# PowerStage.net
KiCad netlist of a schematic drawn in Altium Designer
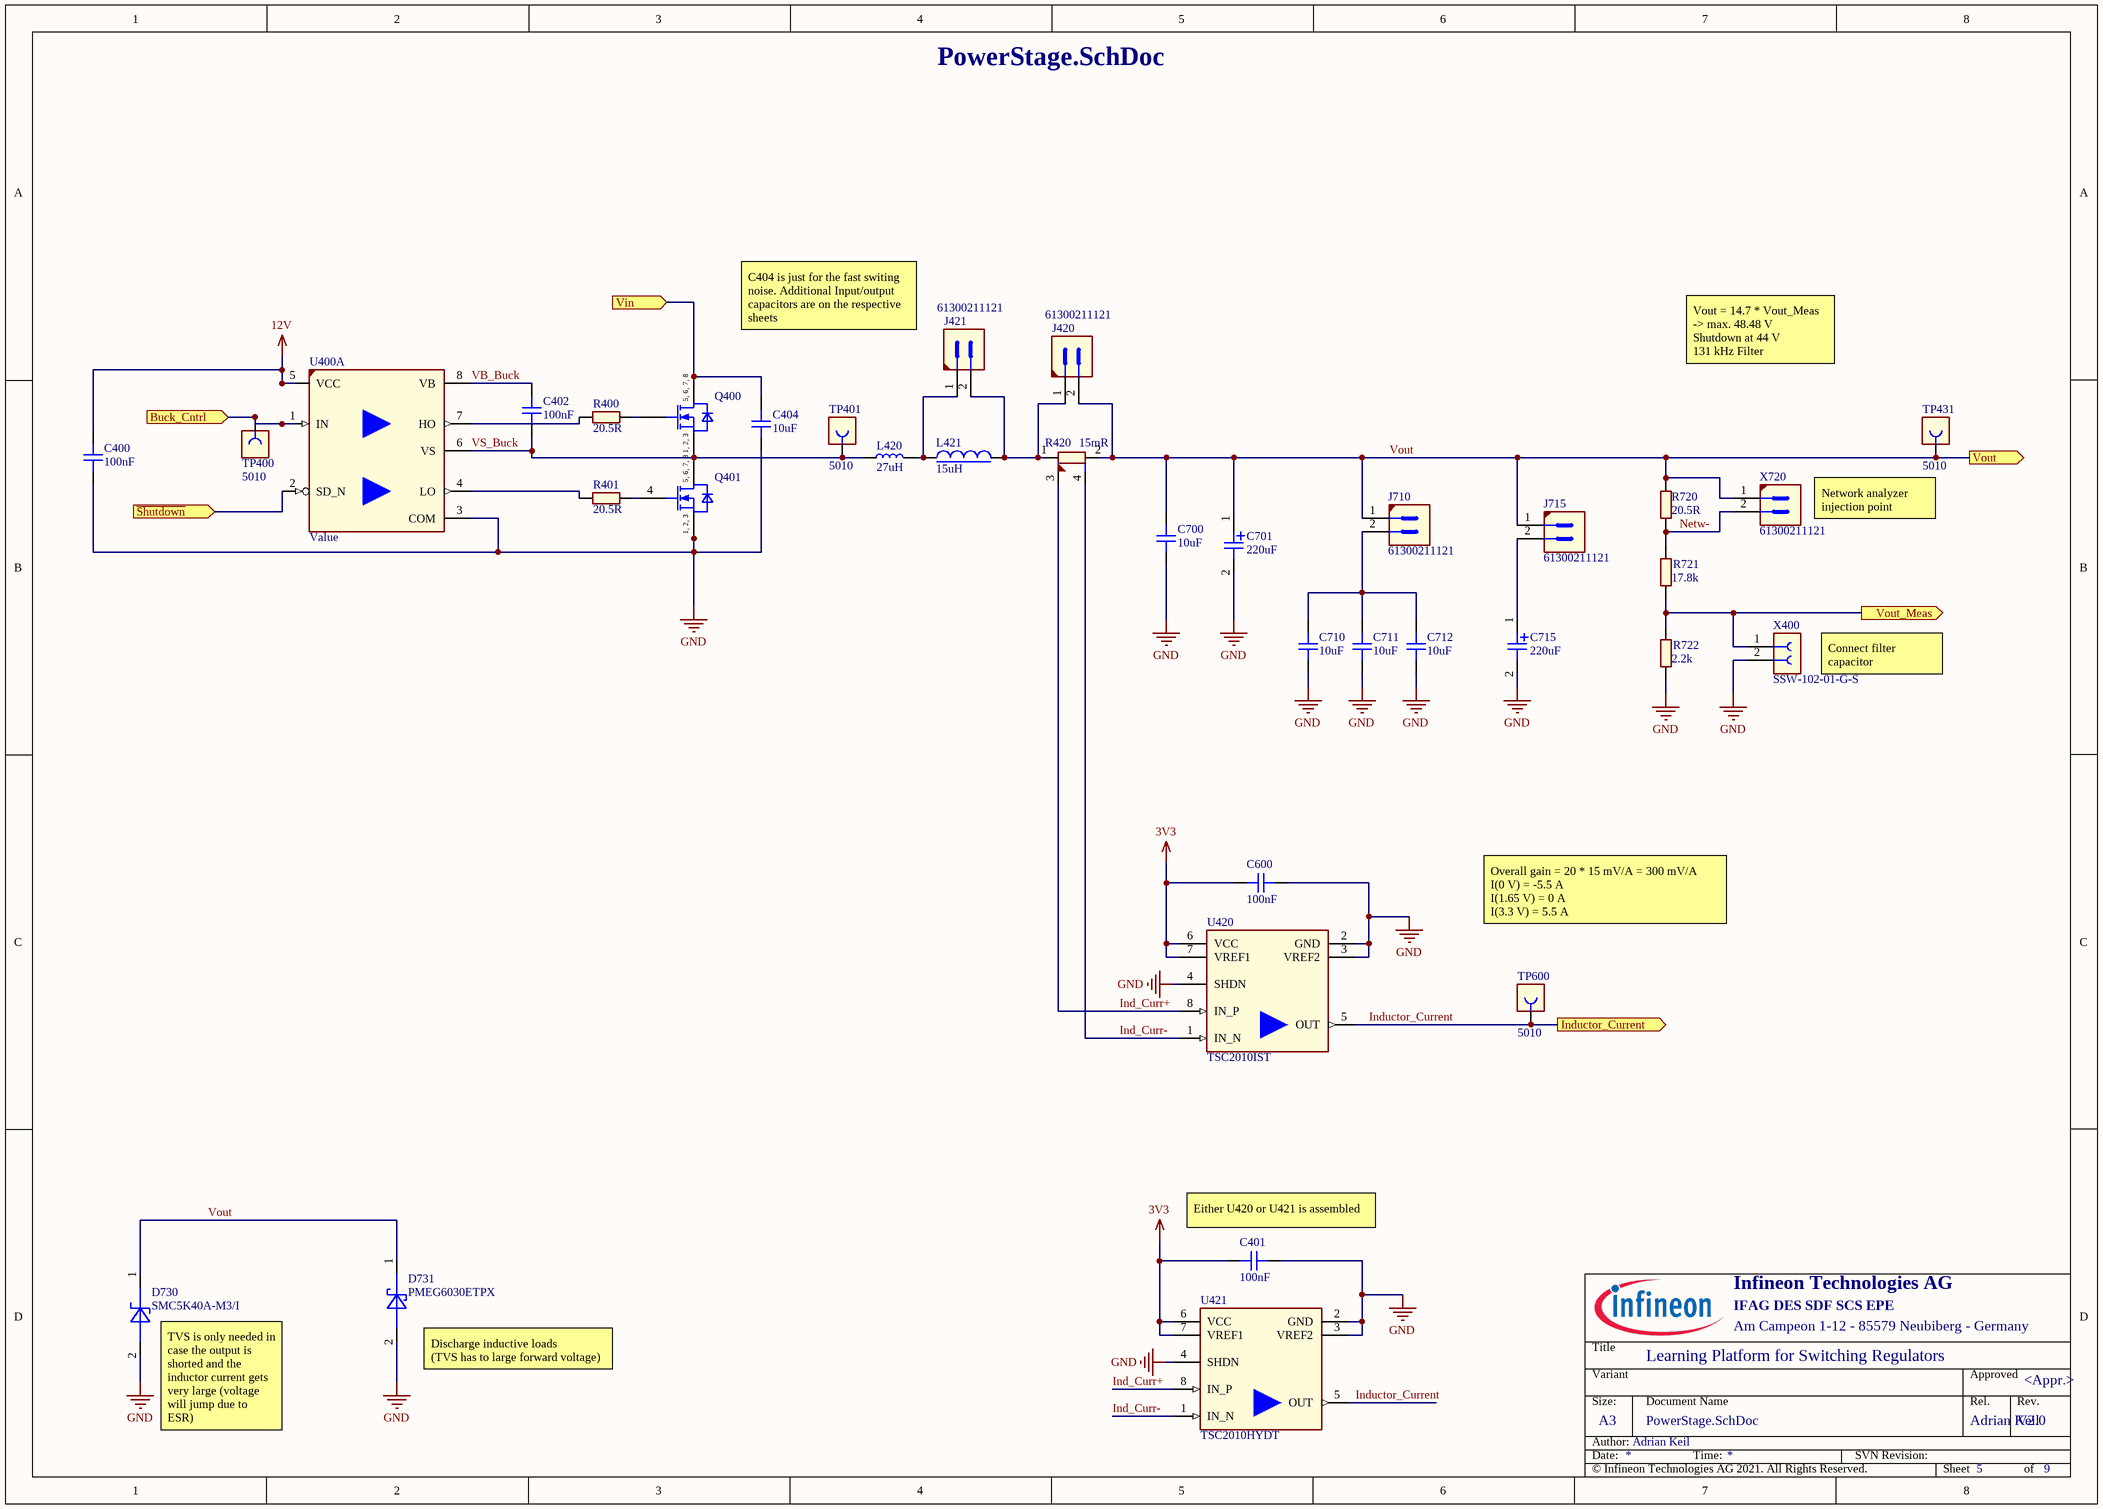
[diagram p0: PowerStage.SchDoc]

(export (version "E")
  (design (tool "Eeschema 10.0.6"))
  (components
    (comp (ref "C400")
      (value "100nF")
      (footprint "CAPC3216X125N-0")
      (description "CAP / CERA / 100nF / 50V / 10% / X7R (EIA) / -55°C to 125°C / 1206(3216) / SMD / -")
      (fields (field (name "LEGACY PARTNUMBER") "CAP01005660") (field (name "MANUFACTURER") "MuRata"))
      (libsource (lib "PCBLibraryData") (part "CAP-SGL-STD-02P_00000001"))
    )
    (comp (ref "C401")
      (value "100nF")
      (footprint "CAPC3216X125N-0")
      (description "CAP / CERA / 100nF / 50V / 10% / X7R (EIA) / -55°C to 125°C / 1206(3216) / SMD / -")
      (fields (field (name "LEGACY PARTNUMBER") "CAP01005660") (field (name "MANUFACTURER") "MuRata"))
      (libsource (lib "PCBLibraryData") (part "CAP-SGL-STD-02P_00000001"))
    )
    (comp (ref "C402")
      (value "100nF")
      (footprint "CAPC3216X125N-0")
      (description "CAP / CERA / 100nF / 50V / 10% / X7R (EIA) / -55°C to 125°C / 1206(3216) / SMD / -")
      (fields (field (name "LEGACY PARTNUMBER") "CAP01005660") (field (name "MANUFACTURER") "MuRata"))
      (libsource (lib "PCBLibraryData") (part "CAP-SGL-STD-02P_00000001"))
    )
    (comp (ref "C404")
      (value "10uF")
      (footprint "CAPC3216X190N-1")
      (description "CAP / CERA / 10uF / 50V / 20% / X5R (EIA) / -55°C to 85°C / 1206 (3216) / SMD / -")
      (fields (field (name "MANUFACTURER") "Taiyo Yuden"))
      (libsource (lib "PCBLibraryData") (part "CAP-SGL-STD-02P_00000001"))
    )
    (comp (ref "C600")
      (value "100nF")
      (footprint "CAPC3216X125N-0")
      (description "CAP / CERA / 100nF / 50V / 10% / X7R (EIA) / -55°C to 125°C / 1206(3216) / SMD / -")
      (fields (field (name "LEGACY PARTNUMBER") "CAP01005660") (field (name "MANUFACTURER") "MuRata"))
      (libsource (lib "PCBLibraryData") (part "CAP-SGL-STD-02P_00000001"))
    )
    (comp (ref "C700")
      (value "10uF")
      (footprint "CAPC3216X190N-1")
      (description "CAP / CERA / 10uF / 50V / 20% / X5R (EIA) / -55°C to 85°C / 1206 (3216) / SMD / -")
      (fields (field (name "MANUFACTURER") "Taiyo Yuden"))
      (libsource (lib "PCBLibraryData") (part "CAP-SGL-STD-02P_00000001"))
    )
    (comp (ref "C701")
      (value "220uF")
      (footprint "CAPAE1030X1050N-3")
      (fields (field (name "MANUFACTURER") "Nippon Chemi-Con"))
      (libsource (lib "PCBLibraryData") (part "CAP-SGL-POL-02P_00000002"))
    )
    (comp (ref "C710")
      (value "10uF")
      (footprint "CAPC3216X190N-1")
      (description "CAP / CERA / 10uF / 50V / 20% / X5R (EIA) / -55°C to 85°C / 1206 (3216) / SMD / -")
      (fields (field (name "MANUFACTURER") "Taiyo Yuden"))
      (libsource (lib "PCBLibraryData") (part "CAP-SGL-STD-02P_00000001"))
    )
    (comp (ref "C711")
      (value "10uF")
      (footprint "CAPC3216X190N-1")
      (description "CAP / CERA / 10uF / 50V / 20% / X5R (EIA) / -55°C to 85°C / 1206 (3216) / SMD / -")
      (fields (field (name "MANUFACTURER") "Taiyo Yuden"))
      (libsource (lib "PCBLibraryData") (part "CAP-SGL-STD-02P_00000001"))
    )
    (comp (ref "C712")
      (value "10uF")
      (footprint "CAPC3216X190N-1")
      (description "CAP / CERA / 10uF / 50V / 20% / X5R (EIA) / -55°C to 85°C / 1206 (3216) / SMD / -")
      (fields (field (name "MANUFACTURER") "Taiyo Yuden"))
      (libsource (lib "PCBLibraryData") (part "CAP-SGL-STD-02P_00000001"))
    )
    (comp (ref "C715")
      (value "220uF")
      (footprint "CAPAE1030X1050N-3")
      (fields (field (name "MANUFACTURER") "Nippon Chemi-Con"))
      (libsource (lib "PCBLibraryData") (part "CAP-SGL-POL-02P_00000002"))
    )
    (comp (ref "D730")
      (value "SMC5K40A-M3/I")
      (footprint "DIOM7959X262N")
      (description "Surface Mount Transient Voltage Suppressors, Unidirectional, Very Fast Response Time")
      (fields (field (name "MANUFACTURER") "Vishay"))
      (libsource (lib "PCBLibraryData") (part "d_tvs_a"))
    )
    (comp (ref "D731")
      (value "PMEG6030ETPX")
      (footprint "SODFL4725X110N")
      (description "DIODE SCHOTTKY 60V 3A SOD128")
      (fields (field (name "MANUFACTURER") "Nexperia"))
      (libsource (lib "PCBLibraryData") (part "d_schottky_a"))
    )
    (comp (ref "J420")
      (value "61300211121")
      (footprint "CON-M-THT-61300211121")
      (description "Header, 2.54mm Pitch, 2 pin, Vertical, Single Row")
      (fields
        (field (name "LEGACY PARTNUMBER") "CON01500943")
        (field (name "MANUFACTURER") "Wurth Elektronik")
      )
      (libsource (lib "") (part "Header 2_1"))
    )
    (comp (ref "J421")
      (value "61300211121")
      (footprint "CON-M-THT-61300211121")
      (description "Header, 2.54mm Pitch, 2 pin, Vertical, Single Row")
      (fields
        (field (name "LEGACY PARTNUMBER") "CON01500943")
        (field (name "MANUFACTURER") "Wurth Elektronik")
      )
      (libsource (lib "") (part "Header 2_1"))
    )
    (comp (ref "J710")
      (value "61300211121")
      (footprint "CON-M-THT-61300211121")
      (description "Header, 2.54mm Pitch, 2 pin, Vertical, Single Row")
      (fields
        (field (name "LEGACY PARTNUMBER") "CON01500943")
        (field (name "MANUFACTURER") "Wurth Elektronik")
      )
      (libsource (lib "PCBLibraryData") (part "Header 2"))
    )
    (comp (ref "J715")
      (value "61300211121")
      (footprint "CON-M-THT-61300211121")
      (description "Header, 2.54mm Pitch, 2 pin, Vertical, Single Row")
      (fields
        (field (name "LEGACY PARTNUMBER") "CON01500943")
        (field (name "MANUFACTURER") "Wurth Elektronik")
      )
      (libsource (lib "PCBLibraryData") (part "Header 2"))
    )
    (comp (ref "L420")
      (value "27uH")
      (footprint "INDM120120X1000N")
      (fields (field (name "MANUFACTURER") "Wurth Elektronik"))
      (libsource (lib "PCBLibraryData") (part "IND-SGL-STD-02P_00000015"))
    )
    (comp (ref "L421")
      (value "15uH")
      (footprint "IND-SMD-SRP6060FA")
      (fields (field (name "MANUFACTURER") "Bourns"))
      (libsource (lib "PCBLibraryData") (part "IND-SGL-STD-COR-02P_00000016"))
    )
    (comp (ref "Q400")
      (value "igfet_n_ch_enh_dio_1s2s3s4g5d6d7d8d_8p")
      (footprint "INF-PG-PQFN-5X6BEG")
      (description "HEXFET Power MOSFET, VDS 60V, RDS(on) max 14.4 mO")
      (fields (field (name "MANUFACTURER") "Infineon Technologies"))
      (libsource (lib "") (part "igfet_n_ch_enh_dio_1s2s3s4g5d6d7d8d_8p_1"))
    )
    (comp (ref "Q401")
      (value "igfet_n_ch_enh_dio_1s2s3s4g5d6d7d8d_8p")
      (footprint "INF-PG-PQFN-5X6BEG")
      (description "HEXFET Power MOSFET, VDS 60V, RDS(on) max 14.4 mO")
      (fields (field (name "MANUFACTURER") "Infineon Technologies"))
      (libsource (lib "PCBLibraryData") (part "igfet_n_ch_enh_dio_1s2s3s4g5d6d7d8d_8p"))
    )
    (comp (ref "R400")
      (value "20.5R")
      (footprint "RESC3216X60N")
      (description "RES / STD / 20.5R / 250mW / 1% / 100ppm/K / -55°C to 155°C / 1206(3216) / SMD / -")
      (fields (field (name "LEGACY PARTNUMBER") "RES01802548") (field (name "MANUFACTURER") "Vishay"))
      (libsource (lib "") (part "RES-SGL-STD-02P_00000006_1"))
    )
    (comp (ref "R401")
      (value "20.5R")
      (footprint "RESC3216X60N")
      (description "RES / STD / 20.5R / 250mW / 1% / 100ppm/K / -55°C to 155°C / 1206(3216) / SMD / -")
      (fields (field (name "LEGACY PARTNUMBER") "RES01802548") (field (name "MANUFACTURER") "Vishay"))
      (libsource (lib "") (part "RES-SGL-STD-02P_00000006_1"))
    )
    (comp (ref "R420")
      (value "15mR")
      (footprint "RES-SMD-L4T12")
      (description "RES / STD / 15mR / 500mW / 1% / 75ppm/K / -55°C to 155°C / 1206 (3216) / SMD / -")
      (fields (field (name "MANUFACTURER") "Ohmite"))
      (libsource (lib "PCBLibraryData") (part "RES-SHT-STD-04P_00097BE5"))
    )
    (comp (ref "R720")
      (value "20.5R")
      (footprint "RESC3216X60N")
      (description "RES / STD / 20.5R / 250mW / 1% / 100ppm/K / -55°C to 155°C / 1206(3216) / SMD / -")
      (fields (field (name "LEGACY PARTNUMBER") "RES01802548") (field (name "MANUFACTURER") "Vishay"))
      (libsource (lib "PCBLibraryData") (part "RES-SGL-STD-02P_00000006"))
    )
    (comp (ref "R721")
      (value "17.8k")
      (footprint "RESC3216X60N")
      (description "RES / STD / 17.8k / 250mW / 1% / 100ppm/K / -55°C to 155°C / 1206(3216) / SMD / -")
      (fields (field (name "LEGACY PARTNUMBER") "RES01802883") (field (name "MANUFACTURER") "Vishay"))
      (libsource (lib "PCBLibraryData") (part "RES-SGL-STD-02P_00000006"))
    )
    (comp (ref "R722")
      (value "2.2k")
      (footprint "RESC3216X60N")
      (description "RES / STD / 2.2k / 250mW / 1% / 100ppm/K / -55°C to 155°C / 1206(3216) / SMD / -")
      (fields (field (name "LEGACY PARTNUMBER") "RES01802779") (field (name "MANUFACTURER") "Vishay"))
      (libsource (lib "") (part "RES-SGL-STD-02P_00000006_2"))
    )
    (comp (ref "TP400")
      (value "5010")
      (footprint "CON-THT-TP-5010")
      (description "PC Test Point-Multipurpose THT, Red")
      (fields
        (field (name "LEGACY PARTNUMBER") "CON01500529")
        (field (name "MANUFACTURER") "Keystone Electronics Corp.")
      )
      (libsource (lib "") (part "connector_1_f_1"))
    )
    (comp (ref "TP401")
      (value "5010")
      (footprint "CON-THT-TP-5010")
      (description "PC Test Point-Multipurpose THT, Red")
      (fields
        (field (name "LEGACY PARTNUMBER") "CON01500529")
        (field (name "MANUFACTURER") "Keystone Electronics Corp.")
      )
      (libsource (lib "PCBLibraryData") (part "connector_1_f"))
    )
    (comp (ref "TP431")
      (value "5010")
      (footprint "CON-THT-TP-5010")
      (description "PC Test Point-Multipurpose THT, Red")
      (fields
        (field (name "LEGACY PARTNUMBER") "CON01500529")
        (field (name "MANUFACTURER") "Keystone Electronics Corp.")
      )
      (libsource (lib "PCBLibraryData") (part "connector_1_f"))
    )
    (comp (ref "TP600")
      (value "5010")
      (footprint "CON-THT-TP-5010")
      (description "PC Test Point-Multipurpose THT, Red")
      (fields
        (field (name "LEGACY PARTNUMBER") "CON01500529")
        (field (name "MANUFACTURER") "Keystone Electronics Corp.")
      )
      (libsource (lib "PCBLibraryData") (part "connector_1_f"))
    )
    (comp (ref "U400")
      (value "Value")
      (footprint "SOIC127P600X172-8N-1-V")
      (description "Driving IGBTs, enhancement mode N-Channel MOSFETs in various power electronic applications")
      (fields (field (name "MANUFACTURER") "Infineon Technologies"))
      (libsource (lib "PCBLibraryData") (part "2ED2184S06F"))
    )
    (comp (ref "U420")
      (value "TSC2010IST")
      (footprint "SOIC127P600X175-8N-16")
      (description "Precision bidirectional current sense amplifier")
      (fields (field (name "MANUFACTURER") "STMicroelectronics"))
      (libsource (lib "PCBLibraryData") (part "TSC201XHYDT"))
    )
    (comp (ref "U421")
      (value "TSC2010HYDT")
      (footprint "SOIC127P600X175-8N-16")
      (description "Precision bidirectional current sense amplifier")
      (fields (field (name "MANUFACTURER") "STMicroelectronics"))
      (libsource (lib "PCBLibraryData") (part "TSC201XHYDT"))
    )
    (comp (ref "X400")
      (value "SSW-102-01-G-S")
      (footprint "CON-F-THT-SSW-102-01-G-S")
      (description "Through Hole .025'' SQ Post Socket, 2.54mm pitch, 2 Pins")
      (fields (field (name "MANUFACTURER") "Samtec"))
      (libsource (lib "PCBLibraryData") (part "Socket 2"))
    )
    (comp (ref "X720")
      (value "61300211121")
      (footprint "CON-M-THT-61300211121")
      (description "Header, 2.54mm Pitch, 2 pin, Vertical, Single Row")
      (fields
        (field (name "LEGACY PARTNUMBER") "CON01500943")
        (field (name "MANUFACTURER") "Wurth Elektronik")
      )
      (libsource (lib "PCBLibraryData") (part "Header 2"))
    )
  )
  (nets
    (net (code "1") (name "/Buck_Cntrl") (class "Default")
      (node (ref "TP400") (pin "1") (pinfunction "1_1") (pintype "passive"))
      (node (ref "U400") (pin "1") (pinfunction "IN_1") (pintype "input"))
    )
    (net (code "2") (name "/Ind_Curr+") (class "Default")
      (node (ref "R420") (pin "3") (pinfunction "I1_3") (pintype "passive"))
      (node (ref "U420") (pin "8") (pinfunction "IN_P_8") (pintype "input"))
      (node (ref "U421") (pin "8") (pinfunction "IN_P_8") (pintype "input"))
    )
    (net (code "3") (name "/Ind_Curr-") (class "Default")
      (node (ref "R420") (pin "4") (pinfunction "I2_4") (pintype "passive"))
      (node (ref "U420") (pin "1") (pinfunction "IN_N_1") (pintype "input"))
      (node (ref "U421") (pin "1") (pinfunction "IN_N_1") (pintype "input"))
    )
    (net (code "4") (name "/Inductor_Current") (class "Default")
      (node (ref "TP600") (pin "1") (pinfunction "1_1") (pintype "passive"))
      (node (ref "U420") (pin "5") (pinfunction "OUT_5") (pintype "output"))
      (node (ref "U421") (pin "5") (pinfunction "OUT_5") (pintype "output"))
    )
    (net (code "5") (name "/Netw-") (class "Default")
      (node (ref "R720") (pin "1") (pinfunction "1_1") (pintype "passive"))
      (node (ref "R721") (pin "2") (pinfunction "2_2") (pintype "passive"))
      (node (ref "X720") (pin "2") (pinfunction "2_2") (pintype "passive"))
    )
    (net (code "6") (name "/Shutdown") (class "Default")
      (node (ref "U400") (pin "2") (pinfunction "SD_N_2") (pintype "input"))
    )
    (net (code "7") (name "/VB_Buck") (class "Default")
      (node (ref "C402") (pin "2") (pinfunction "2_2") (pintype "passive"))
      (node (ref "U400") (pin "8") (pinfunction "VB_8") (pintype "power_in"))
    )
    (net (code "8") (name "/VS_Buck") (class "Default")
      (node (ref "C402") (pin "1") (pinfunction "1_1") (pintype "passive"))
      (node (ref "L420") (pin "1") (pinfunction "1_1") (pintype "passive"))
      (node (ref "Q400") (pin "1") (pinfunction "SOURCE_1") (pintype "passive"))
      (node (ref "Q400") (pin "2") (pinfunction "SOURCE_2") (pintype "passive"))
      (node (ref "Q400") (pin "3") (pinfunction "SOURCE_3") (pintype "passive"))
      (node (ref "Q401") (pin "5") (pinfunction "DRAIN_5") (pintype "passive"))
      (node (ref "Q401") (pin "6") (pinfunction "DRAIN_6") (pintype "passive"))
      (node (ref "Q401") (pin "7") (pinfunction "DRAIN_7") (pintype "passive"))
      (node (ref "Q401") (pin "8") (pinfunction "DRAIN_8") (pintype "passive"))
      (node (ref "TP401") (pin "1") (pinfunction "1_1") (pintype "passive"))
      (node (ref "U400") (pin "6") (pinfunction "VS_6") (pintype "power_in"))
    )
    (net (code "9") (name "/Vin") (class "Default")
      (node (ref "C404") (pin "2") (pinfunction "2_2") (pintype "passive"))
      (node (ref "Q400") (pin "5") (pinfunction "DRAIN_5") (pintype "passive"))
      (node (ref "Q400") (pin "6") (pinfunction "DRAIN_6") (pintype "passive"))
      (node (ref "Q400") (pin "7") (pinfunction "DRAIN_7") (pintype "passive"))
      (node (ref "Q400") (pin "8") (pinfunction "DRAIN_8") (pintype "passive"))
    )
    (net (code "10") (name "/Vout") (class "Default")
      (node (ref "C700") (pin "2") (pinfunction "2_2") (pintype "passive"))
      (node (ref "C701") (pin "1") (pinfunction "1_1") (pintype "passive"))
      (node (ref "D730") (pin "1") (pinfunction "CATHODE_1") (pintype "passive"))
      (node (ref "D731") (pin "1") (pinfunction "Cathode_1") (pintype "passive"))
      (node (ref "J420") (pin "2") (pinfunction "2_2") (pintype "passive"))
      (node (ref "J710") (pin "1") (pinfunction "1_1") (pintype "passive"))
      (node (ref "J715") (pin "1") (pinfunction "1_1") (pintype "passive"))
      (node (ref "R420") (pin "2") (pinfunction "V2_2") (pintype "passive"))
      (node (ref "R720") (pin "2") (pinfunction "2_2") (pintype "passive"))
      (node (ref "TP431") (pin "1") (pinfunction "1_1") (pintype "passive"))
      (node (ref "X720") (pin "1") (pinfunction "1_1") (pintype "passive"))
    )
    (net (code "11") (name "/Vout_Meas") (class "Default")
      (node (ref "R721") (pin "1") (pinfunction "1_1") (pintype "passive"))
      (node (ref "R722") (pin "1") (pinfunction "1_1") (pintype "passive"))
      (node (ref "X400") (pin "1") (pinfunction "1_1") (pintype "passive"))
    )
    (net (code "12") (name "3V3") (class "Default")
      (node (ref "C401") (pin "2") (pinfunction "2_2") (pintype "passive"))
      (node (ref "C600") (pin "2") (pinfunction "2_2") (pintype "passive"))
      (node (ref "U420") (pin "6") (pinfunction "VCC_6") (pintype "power_in"))
      (node (ref "U420") (pin "7") (pinfunction "VREF1_7") (pintype "power_in"))
      (node (ref "U421") (pin "6") (pinfunction "VCC_6") (pintype "power_in"))
      (node (ref "U421") (pin "7") (pinfunction "VREF1_7") (pintype "power_in"))
    )
    (net (code "13") (name "12V") (class "Default")
      (node (ref "C400") (pin "2") (pinfunction "2_2") (pintype "passive"))
      (node (ref "U400") (pin "5") (pinfunction "VCC_5") (pintype "power_in"))
    )
    (net (code "14") (name "GND") (class "Default")
      (node (ref "C400") (pin "1") (pinfunction "1_1") (pintype "passive"))
      (node (ref "C401") (pin "1") (pinfunction "1_1") (pintype "passive"))
      (node (ref "C404") (pin "1") (pinfunction "1_1") (pintype "passive"))
      (node (ref "C600") (pin "1") (pinfunction "1_1") (pintype "passive"))
      (node (ref "C700") (pin "1") (pinfunction "1_1") (pintype "passive"))
      (node (ref "C701") (pin "2") (pinfunction "2_2") (pintype "passive"))
      (node (ref "C710") (pin "1") (pinfunction "1_1") (pintype "passive"))
      (node (ref "C711") (pin "1") (pinfunction "1_1") (pintype "passive"))
      (node (ref "C712") (pin "1") (pinfunction "1_1") (pintype "passive"))
      (node (ref "C715") (pin "2") (pinfunction "2_2") (pintype "passive"))
      (node (ref "D730") (pin "2") (pinfunction "ANODE_2") (pintype "passive"))
      (node (ref "D731") (pin "2") (pinfunction "Anode_2") (pintype "passive"))
      (node (ref "Q401") (pin "1") (pinfunction "SOURCE_1") (pintype "passive"))
      (node (ref "Q401") (pin "2") (pinfunction "SOURCE_2") (pintype "passive"))
      (node (ref "Q401") (pin "3") (pinfunction "SOURCE_3") (pintype "passive"))
      (node (ref "R722") (pin "2") (pinfunction "2_2") (pintype "passive"))
      (node (ref "U400") (pin "3") (pinfunction "COM_3") (pintype "passive"))
      (node (ref "U420") (pin "2") (pinfunction "GND_2") (pintype "power_in"))
      (node (ref "U420") (pin "3") (pinfunction "VREF2_3") (pintype "power_in"))
      (node (ref "U420") (pin "4") (pinfunction "SHDN_4") (pintype "passive"))
      (node (ref "U421") (pin "2") (pinfunction "GND_2") (pintype "power_in"))
      (node (ref "U421") (pin "3") (pinfunction "VREF2_3") (pintype "power_in"))
      (node (ref "U421") (pin "4") (pinfunction "SHDN_4") (pintype "passive"))
      (node (ref "X400") (pin "2") (pinfunction "2_2") (pintype "passive"))
    )
    (net (code "15") (name "Net-(C710-Pad2)") (class "Default")
      (node (ref "C710") (pin "2") (pinfunction "2_2") (pintype "passive"))
      (node (ref "C711") (pin "2") (pinfunction "2_2") (pintype "passive"))
      (node (ref "C712") (pin "2") (pinfunction "2_2") (pintype "passive"))
      (node (ref "J710") (pin "2") (pinfunction "2_2") (pintype "passive"))
    )
    (net (code "16") (name "Net-(C715-Pad1)") (class "Default")
      (node (ref "C715") (pin "1") (pinfunction "1_1") (pintype "passive"))
      (node (ref "J715") (pin "2") (pinfunction "2_2") (pintype "passive"))
    )
    (net (code "17") (name "Net-(J421-Pad1)") (class "Default")
      (node (ref "J421") (pin "1") (pinfunction "1_1") (pintype "passive"))
      (node (ref "L420") (pin "2") (pinfunction "2_2") (pintype "passive"))
      (node (ref "L421") (pin "1") (pinfunction "1_1") (pintype "passive"))
    )
    (net (code "18") (name "Net-(Q400-GATE)") (class "Default")
      (node (ref "Q400") (pin "4") (pinfunction "GATE_4") (pintype "passive"))
      (node (ref "R400") (pin "1") (pinfunction "1_1") (pintype "passive"))
    )
    (net (code "19") (name "Net-(Q401-GATE)") (class "Default")
      (node (ref "Q401") (pin "4") (pinfunction "GATE_4") (pintype "passive"))
      (node (ref "R401") (pin "1") (pinfunction "1_1") (pintype "passive"))
    )
    (net (code "20") (name "Net-(R420-V1)") (class "Default")
      (node (ref "J420") (pin "1") (pinfunction "1_1") (pintype "passive"))
      (node (ref "J421") (pin "2") (pinfunction "2_2") (pintype "passive"))
      (node (ref "L421") (pin "2") (pinfunction "2_2") (pintype "passive"))
      (node (ref "R420") (pin "1") (pinfunction "V1_1") (pintype "passive"))
    )
    (net (code "21") (name "Net-(U400-HO)") (class "Default")
      (node (ref "R400") (pin "2") (pinfunction "2_2") (pintype "passive"))
      (node (ref "U400") (pin "7") (pinfunction "HO_7") (pintype "output"))
    )
    (net (code "22") (name "Net-(U400-LO)") (class "Default")
      (node (ref "R401") (pin "2") (pinfunction "2_2") (pintype "passive"))
      (node (ref "U400") (pin "4") (pinfunction "LO_4") (pintype "output"))
    )
  )
)
